# Saw_Tooth_and_PWM_Generator.net
KiCad netlist of a schematic drawn in Altium Designer
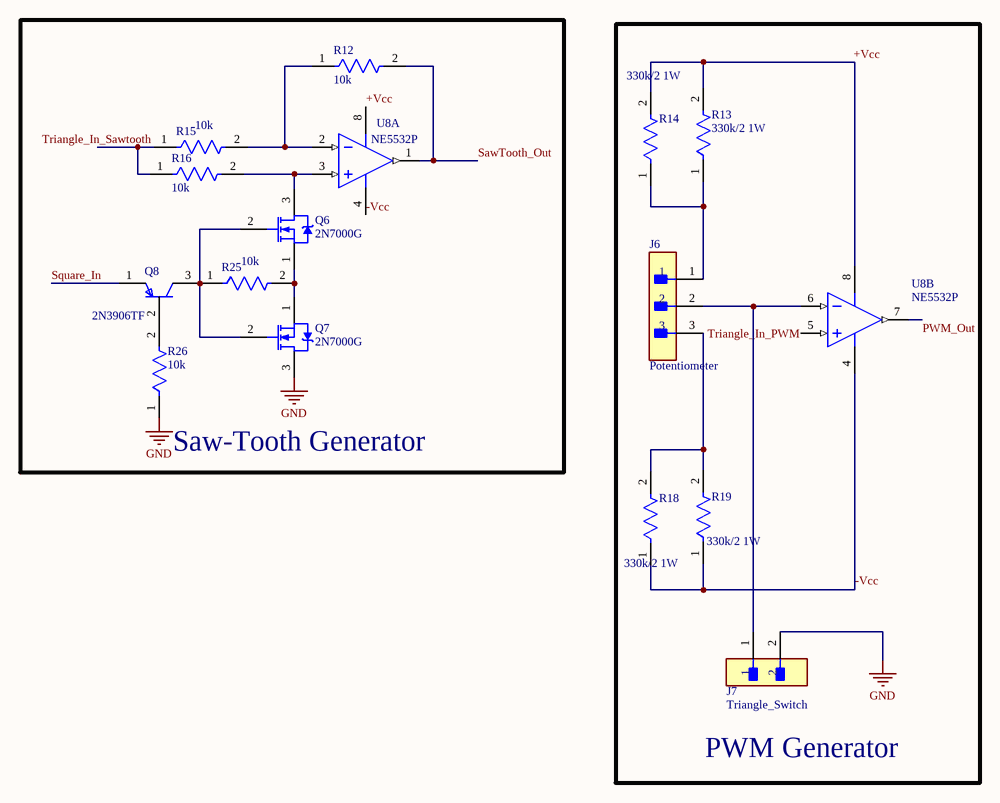
[diagram p0: Saw Tooth and PWM Generator.SchDoc]

(export (version "E")
  (design (tool "Eeschema 10.0.6"))
  (components
    (comp (ref "J6")
      (value "Potentiometer")
      (footprint "FP-440054-3-MFG")
      (description "CONN HEADER VERT 3POS 2MM")
      (fields
        (field (name "OCTOPART") "https://octopart.com/440054-3-te+connectivity-40394845")
        (field (name "MANUFACTURER") "TE Connectivity")
      )
      (libsource (lib "Altium Content Vault") (part "0d3f023dd272f625e17a2be33dea85f"))
    )
    (comp (ref "J7")
      (value "Triangle_Switch")
      (footprint "FP-B2B-XH-A_LF_SN-MFG")
      (description "CONN HEADER VERT 2POS 2.5MM")
      (libsource (lib "Altium Content Vault") (part "3bc925449376181038e59eaffc5286c"))
    )
    (comp (ref "Q6")
      (value "2N7000G")
      (footprint "ONSC-TO-92-3-29-11")
      (description "Small Signal MOSFET, 200 mA, 60 V, N-Channel, 3-Pin TO-92, Pb-Free, Bulk Box")
      (fields (field (name "MANUFACTURER") "On Semiconductor"))
      (libsource (lib "Altium Content Vault") (part "ONSC-NMOS-S1G2D3-3"))
    )
    (comp (ref "Q7")
      (value "2N7000G")
      (footprint "ONSC-TO-92-3-29-11")
      (description "Small Signal MOSFET, 200 mA, 60 V, N-Channel, 3-Pin TO-92, Pb-Free, Bulk Box")
      (fields (field (name "MANUFACTURER") "On Semiconductor"))
      (libsource (lib "Altium Content Vault") (part "ONSC-NMOS-S1G2D3-3"))
    )
    (comp (ref "Q8")
      (value "2N3906TF")
      (footprint "FP-135AR-MFG")
      (description "2N3906TF Small Signal Bipolar Transistor, 0.2A I(C), 40V V(BR)CEO, 1-Element, PNP, Silicon, TO-92")
      (libsource (lib "Altium Content Vault") (part "40d2b7e180a7bcff784209620afba3e"))
    )
    (comp (ref "R12")
      (value "10k")
      (footprint "FP-VR37-MFG")
      (description "RES 1.2M OHM 5% 1/2W AXIAL")
      (fields (field (name "TOLERANCE") "5%"))
      (libsource (lib "Altium Content Vault") (part "1029c3af85768c4190bb7ad29bc67b5"))
    )
    (comp (ref "R13")
      (value "330k/2 1W")
      (footprint "FP-RR01-MFG")
      (description "RES 100K OHM 5% 1W AXIAL")
      (fields (field (name "TOLERANCE") "5%"))
      (libsource (lib "Altium Content Vault") (part "1029c3af85768c4190bb7ad29bc67b5"))
    )
    (comp (ref "R14")
      (value "330k/2 1W")
      (footprint "FP-RR01-MFG")
      (description "RES 100K OHM 5% 1W AXIAL")
      (fields (field (name "TOLERANCE") "5%"))
      (libsource (lib "Altium Content Vault") (part "1029c3af85768c4190bb7ad29bc67b5"))
    )
    (comp (ref "R15")
      (value "10k")
      (footprint "FP-VR37-MFG")
      (description "RES 1.2M OHM 5% 1/2W AXIAL")
      (fields (field (name "TOLERANCE") "5%"))
      (libsource (lib "Altium Content Vault") (part "1029c3af85768c4190bb7ad29bc67b5"))
    )
    (comp (ref "R16")
      (value "10k")
      (footprint "FP-VR37-MFG")
      (description "RES 1.2M OHM 5% 1/2W AXIAL")
      (fields (field (name "TOLERANCE") "5%"))
      (libsource (lib "Altium Content Vault") (part "1029c3af85768c4190bb7ad29bc67b5"))
    )
    (comp (ref "R18")
      (value "330k/2 1W")
      (footprint "FP-RR01-MFG")
      (description "RES 100K OHM 5% 1W AXIAL")
      (fields (field (name "TOLERANCE") "5%"))
      (libsource (lib "Altium Content Vault") (part "1029c3af85768c4190bb7ad29bc67b5"))
    )
    (comp (ref "R19")
      (value "330k/2 1W")
      (footprint "FP-RR01-MFG")
      (description "RES 100K OHM 5% 1W AXIAL")
      (fields (field (name "TOLERANCE") "5%"))
      (libsource (lib "Altium Content Vault") (part "1029c3af85768c4190bb7ad29bc67b5"))
    )
    (comp (ref "R25")
      (value "10k")
      (footprint "FP-VR37-MFG")
      (description "RES 1.2M OHM 5% 1/2W AXIAL")
      (fields (field (name "TOLERANCE") "5%"))
      (libsource (lib "Altium Content Vault") (part "1029c3af85768c4190bb7ad29bc67b5"))
    )
    (comp (ref "R26")
      (value "10k")
      (footprint "FP-VR37-MFG")
      (description "RES 1.2M OHM 5% 1/2W AXIAL")
      (fields (field (name "TOLERANCE") "5%"))
      (libsource (lib "Altium Content Vault") (part "1029c3af85768c4190bb7ad29bc67b5"))
    )
    (comp (ref "U8")
      (value "NE5532P")
      (footprint "P0008A")
      (fields (field (name "MANUFACTURER") "Texas Instruments"))
      (libsource (lib "Altium Content Vault") (part "TI-AMP-D6-2-8_D"))
    )
  )
  (nets
    (net (code "1") (name "/+Vcc") (class "Default")
      (node (ref "R13") (pin "2") (pinfunction "2_2") (pintype "passive"))
      (node (ref "R14") (pin "2") (pinfunction "2_2") (pintype "passive"))
      (node (ref "U8") (pin "8") (pinfunction "VCC+_8") (pintype "power_in"))
    )
    (net (code "2") (name "/-Vcc") (class "Default")
      (node (ref "R18") (pin "1") (pinfunction "1_1") (pintype "passive"))
      (node (ref "R19") (pin "1") (pinfunction "1_1") (pintype "passive"))
      (node (ref "U8") (pin "4") (pinfunction "VCC-_4") (pintype "power_in"))
    )
    (net (code "3") (name "/PWM_Out") (class "Default")
      (node (ref "U8") (pin "7") (pinfunction "OUT2_7") (pintype "output"))
    )
    (net (code "4") (name "/SawTooth_Out") (class "Default")
      (node (ref "R12") (pin "2") (pinfunction "2_2") (pintype "passive"))
      (node (ref "U8") (pin "1") (pinfunction "OUT1_1") (pintype "output"))
    )
    (net (code "5") (name "/Square_In") (class "Default")
      (node (ref "Q8") (pin "1") (pinfunction "E_1") (pintype "passive"))
    )
    (net (code "6") (name "/Triangle_In_PWM") (class "Default")
      (node (ref "U8") (pin "5") (pinfunction "IN2+_5") (pintype "input"))
    )
    (net (code "7") (name "/Triangle_In_Sawtooth") (class "Default")
      (node (ref "R15") (pin "1") (pinfunction "1_1") (pintype "passive"))
      (node (ref "R16") (pin "1") (pinfunction "1_1") (pintype "passive"))
    )
    (net (code "8") (name "GND") (class "Default")
      (node (ref "J7") (pin "2") (pinfunction "2_2") (pintype "passive"))
      (node (ref "Q7") (pin "3") (pinfunction "D_3") (pintype "passive"))
      (node (ref "R26") (pin "1") (pinfunction "1_1") (pintype "passive"))
    )
    (net (code "9") (name "Net-(J6-Pad1)") (class "Default")
      (node (ref "J6") (pin "1") (pinfunction "1_1") (pintype "passive"))
      (node (ref "R13") (pin "1") (pinfunction "1_1") (pintype "passive"))
      (node (ref "R14") (pin "1") (pinfunction "1_1") (pintype "passive"))
    )
    (net (code "10") (name "Net-(J6-Pad3)") (class "Default")
      (node (ref "J6") (pin "3") (pinfunction "3_3") (pintype "passive"))
      (node (ref "R18") (pin "2") (pinfunction "2_2") (pintype "passive"))
      (node (ref "R19") (pin "2") (pinfunction "2_2") (pintype "passive"))
    )
    (net (code "11") (name "Net-(Q6-D)") (class "Default")
      (node (ref "Q6") (pin "3") (pinfunction "D_3") (pintype "passive"))
      (node (ref "R16") (pin "2") (pinfunction "2_2") (pintype "passive"))
      (node (ref "U8") (pin "3") (pinfunction "IN1+_3") (pintype "input"))
    )
    (net (code "12") (name "Net-(Q6-G)") (class "Default")
      (node (ref "Q6") (pin "2") (pinfunction "G_2") (pintype "passive"))
      (node (ref "Q7") (pin "2") (pinfunction "G_2") (pintype "passive"))
      (node (ref "Q8") (pin "3") (pinfunction "C_3") (pintype "passive"))
      (node (ref "R25") (pin "1") (pinfunction "1_1") (pintype "passive"))
    )
    (net (code "13") (name "Net-(Q6-S)") (class "Default")
      (node (ref "Q6") (pin "1") (pinfunction "S_1") (pintype "passive"))
      (node (ref "Q7") (pin "1") (pinfunction "S_1") (pintype "passive"))
      (node (ref "R25") (pin "2") (pinfunction "2_2") (pintype "passive"))
    )
    (net (code "14") (name "Net-(Q8-B)") (class "Default")
      (node (ref "Q8") (pin "2") (pinfunction "B_2") (pintype "passive"))
      (node (ref "R26") (pin "2") (pinfunction "2_2") (pintype "passive"))
    )
    (net (code "15") (name "Net-(U8A-IN1-)") (class "Default")
      (node (ref "R12") (pin "1") (pinfunction "1_1") (pintype "passive"))
      (node (ref "R15") (pin "2") (pinfunction "2_2") (pintype "passive"))
      (node (ref "U8") (pin "2") (pinfunction "IN1-_2") (pintype "input"))
    )
    (net (code "16") (name "Net-(U8B-IN2-)") (class "Default")
      (node (ref "J6") (pin "2") (pinfunction "2_2") (pintype "passive"))
      (node (ref "J7") (pin "1") (pinfunction "1_1") (pintype "passive"))
      (node (ref "U8") (pin "6") (pinfunction "IN2-_6") (pintype "input"))
    )
  )
)
